# rev19schem.net
KiCad netlist of a schematic drawn in EAGLE
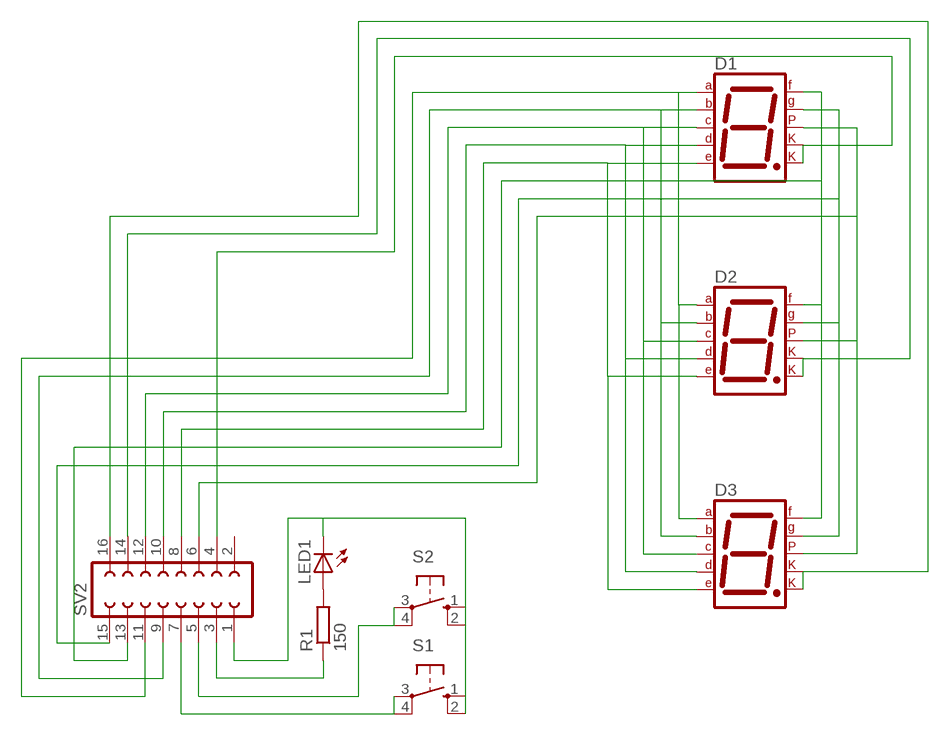
[diagram p0: schematic, sheet 1]

(export (version "E")
  (design (tool "Eeschema 10.0.6"))
  (components
    (comp (ref "D1")
      (value "7SEG-CK")
      (footprint "eagle-import:7SEG-13")
      (libsource (lib "eagle-import") (part "7SEG-CK"))
    )
    (comp (ref "D2")
      (value "7SEG-CK")
      (footprint "eagle-import:7SEG-13")
      (libsource (lib "eagle-import") (part "7SEG-CK"))
    )
    (comp (ref "D3")
      (value "7SEG-CK")
      (footprint "eagle-import:7SEG-13")
      (libsource (lib "eagle-import") (part "7SEG-CK"))
    )
    (comp (ref "LED1")
      (value "LED5MM")
      (footprint "eagle-import:LED5MM")
      (libsource (lib "eagle-import") (part "LED5MM"))
    )
    (comp (ref "R1")
      (value "150")
      (footprint "eagle-import:R0805")
      (libsource (lib "eagle-import") (part "R-EU_R0805"))
    )
    (comp (ref "S1")
      (value "10-XX")
      (footprint "eagle-import:B3F-10XX")
      (fields (field (name "MPN") "B3F-1000"))
      (libsource (lib "eagle-import") (part "10-XX"))
    )
    (comp (ref "S2")
      (value "10-XX")
      (footprint "eagle-import:B3F-10XX")
      (fields (field (name "MPN") "B3F-1000"))
      (libsource (lib "eagle-import") (part "10-XX"))
    )
    (comp (ref "SV2")
      (value "FE08-2")
      (footprint "eagle-import:FE08-2")
      (libsource (lib "eagle-import") (part "FE08-2"))
    )
  )
  (nets
    (net (code "1") (name "Net-(D1-A)") (class "Default")
      (node (ref "D1") (pin "7") (pinfunction "A_7") (pintype "passive"))
      (node (ref "D2") (pin "7") (pinfunction "A_7") (pintype "passive"))
      (node (ref "D3") (pin "7") (pinfunction "A_7") (pintype "passive"))
      (node (ref "SV2") (pin "11") (pinfunction "11_11") (pintype "passive"))
    )
    (net (code "2") (name "Net-(D1-B)") (class "Default")
      (node (ref "D1") (pin "6") (pinfunction "B_6") (pintype "passive"))
      (node (ref "D2") (pin "6") (pinfunction "B_6") (pintype "passive"))
      (node (ref "D3") (pin "6") (pinfunction "B_6") (pintype "passive"))
      (node (ref "SV2") (pin "9") (pinfunction "9_9") (pintype "passive"))
    )
    (net (code "3") (name "Net-(D1-C)") (class "Default")
      (node (ref "D1") (pin "4") (pinfunction "C_4") (pintype "passive"))
      (node (ref "D2") (pin "4") (pinfunction "C_4") (pintype "passive"))
      (node (ref "D3") (pin "4") (pinfunction "C_4") (pintype "passive"))
      (node (ref "SV2") (pin "12") (pinfunction "12_12") (pintype "passive"))
    )
    (net (code "4") (name "Net-(D1-CK1)") (class "Default")
      (node (ref "D1") (pin "3") (pinfunction "CK1_3") (pintype "passive"))
      (node (ref "D1") (pin "8") (pinfunction "CK2_8") (pintype "passive"))
      (node (ref "SV2") (pin "4") (pinfunction "4_4") (pintype "passive"))
    )
    (net (code "5") (name "Net-(D1-D)") (class "Default")
      (node (ref "D1") (pin "2") (pinfunction "D_2") (pintype "passive"))
      (node (ref "D2") (pin "2") (pinfunction "D_2") (pintype "passive"))
      (node (ref "D3") (pin "2") (pinfunction "D_2") (pintype "passive"))
      (node (ref "SV2") (pin "10") (pinfunction "10_10") (pintype "passive"))
    )
    (net (code "6") (name "Net-(D1-DP)") (class "Default")
      (node (ref "D1") (pin "5") (pinfunction "DP_5") (pintype "passive"))
      (node (ref "D2") (pin "5") (pinfunction "DP_5") (pintype "passive"))
      (node (ref "D3") (pin "5") (pinfunction "DP_5") (pintype "passive"))
      (node (ref "SV2") (pin "6") (pinfunction "6_6") (pintype "passive"))
    )
    (net (code "7") (name "Net-(D1-E)") (class "Default")
      (node (ref "D1") (pin "1") (pinfunction "E_1") (pintype "passive"))
      (node (ref "D2") (pin "1") (pinfunction "E_1") (pintype "passive"))
      (node (ref "D3") (pin "1") (pinfunction "E_1") (pintype "passive"))
      (node (ref "SV2") (pin "8") (pinfunction "8_8") (pintype "passive"))
    )
    (net (code "8") (name "Net-(D1-F)") (class "Default")
      (node (ref "D1") (pin "9") (pinfunction "F_9") (pintype "passive"))
      (node (ref "D2") (pin "9") (pinfunction "F_9") (pintype "passive"))
      (node (ref "D3") (pin "9") (pinfunction "F_9") (pintype "passive"))
      (node (ref "SV2") (pin "13") (pinfunction "13_13") (pintype "passive"))
    )
    (net (code "9") (name "Net-(D1-G)") (class "Default")
      (node (ref "D1") (pin "10") (pinfunction "G_10") (pintype "passive"))
      (node (ref "D2") (pin "10") (pinfunction "G_10") (pintype "passive"))
      (node (ref "D3") (pin "10") (pinfunction "G_10") (pintype "passive"))
      (node (ref "SV2") (pin "15") (pinfunction "15_15") (pintype "passive"))
    )
    (net (code "10") (name "Net-(D2-CK1)") (class "Default")
      (node (ref "D2") (pin "3") (pinfunction "CK1_3") (pintype "passive"))
      (node (ref "D2") (pin "8") (pinfunction "CK2_8") (pintype "passive"))
      (node (ref "SV2") (pin "14") (pinfunction "14_14") (pintype "passive"))
    )
    (net (code "11") (name "Net-(D3-CK1)") (class "Default")
      (node (ref "D3") (pin "3") (pinfunction "CK1_3") (pintype "passive"))
      (node (ref "D3") (pin "8") (pinfunction "CK2_8") (pintype "passive"))
      (node (ref "SV2") (pin "16") (pinfunction "16_16") (pintype "passive"))
    )
    (net (code "12") (name "Net-(LED1-C)") (class "Default")
      (node (ref "LED1") (pin "K") (pinfunction "C_K") (pintype "passive"))
      (node (ref "S1") (pin "1") (pinfunction "S_1") (pintype "passive"))
      (node (ref "S1") (pin "2") (pinfunction "S1_2") (pintype "passive"))
      (node (ref "S2") (pin "1") (pinfunction "S_1") (pintype "passive"))
      (node (ref "S2") (pin "2") (pinfunction "S1_2") (pintype "passive"))
      (node (ref "SV2") (pin "1") (pinfunction "1_1") (pintype "passive"))
    )
    (net (code "13") (name "Net-(LED1-PadA)") (class "Default")
      (node (ref "LED1") (pin "A") (pinfunction "A_A") (pintype "passive"))
      (node (ref "R1") (pin "2") (pinfunction "2_2") (pintype "passive"))
    )
    (net (code "14") (name "Net-(R1-Pad1)") (class "Default")
      (node (ref "R1") (pin "1") (pinfunction "1_1") (pintype "passive"))
      (node (ref "SV2") (pin "3") (pinfunction "3_3") (pintype "passive"))
    )
    (net (code "15") (name "Net-(S1-P)") (class "Default")
      (node (ref "S1") (pin "3") (pinfunction "P_3") (pintype "passive"))
      (node (ref "S1") (pin "4") (pinfunction "P1_4") (pintype "passive"))
      (node (ref "SV2") (pin "7") (pinfunction "7_7") (pintype "passive"))
    )
    (net (code "16") (name "Net-(S2-P)") (class "Default")
      (node (ref "S2") (pin "3") (pinfunction "P_3") (pintype "passive"))
      (node (ref "S2") (pin "4") (pinfunction "P1_4") (pintype "passive"))
      (node (ref "SV2") (pin "5") (pinfunction "5_5") (pintype "passive"))
    )
    (net (code "17") (name "unconnected-(SV2-Pad2)") (class "Default")
      (node (ref "SV2") (pin "2") (pinfunction "2_2") (pintype "passive"))
    )
  )
)
